# MICHA.net
KiCad netlist of a schematic drawn in EAGLE
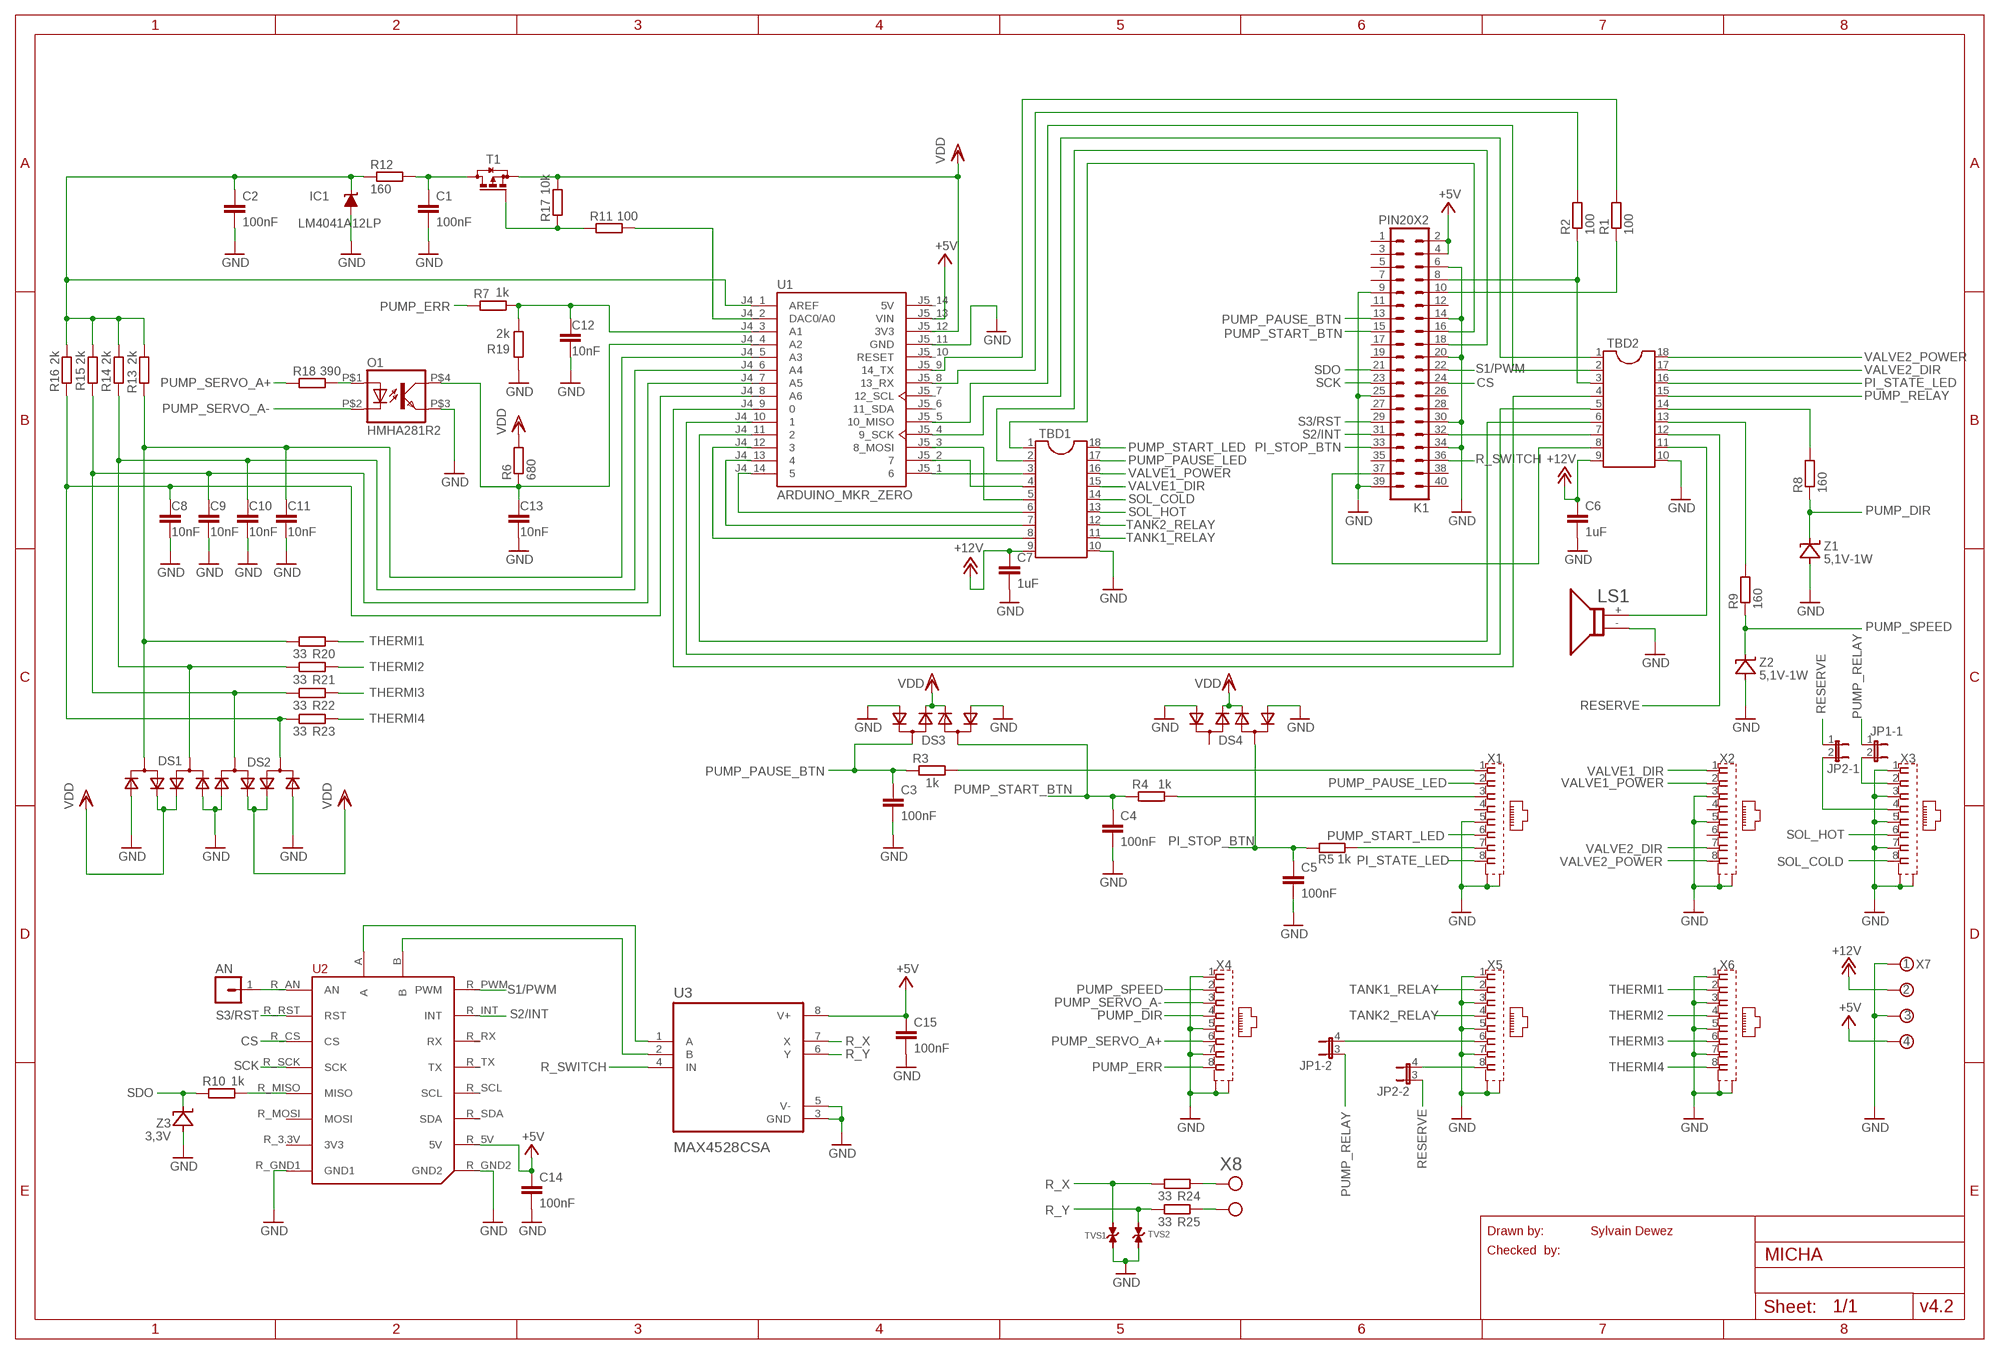
[diagram p0: schematic, sheet 1]

(export (version "E")
  (design (tool "Eeschema 10.0.6"))
  (components
    (comp (ref "AN")
      (value "MA01_PINHEADER")
      (footprint "eagle-import:MA01")
      (libsource (lib "eagle-import") (part "MA01_PINHEADER"))
    )
    (comp (ref "C1")
      (value "100nF")
      (footprint "eagle-import:C1206")
      (libsource (lib "eagle-import") (part "C-EUC1206"))
    )
    (comp (ref "C2")
      (value "100nF")
      (footprint "eagle-import:C1206")
      (libsource (lib "eagle-import") (part "C-EUC1206"))
    )
    (comp (ref "C3")
      (value "100nF")
      (footprint "eagle-import:C1206")
      (libsource (lib "eagle-import") (part "C-EUC1206"))
    )
    (comp (ref "C4")
      (value "100nF")
      (footprint "eagle-import:C1206")
      (libsource (lib "eagle-import") (part "C-EUC1206"))
    )
    (comp (ref "C5")
      (value "100nF")
      (footprint "eagle-import:C1206")
      (libsource (lib "eagle-import") (part "C-EUC1206"))
    )
    (comp (ref "C6")
      (value "1uF")
      (footprint "eagle-import:C1206")
      (libsource (lib "eagle-import") (part "C-EUC1206"))
    )
    (comp (ref "C7")
      (value "1uF")
      (footprint "eagle-import:C1206")
      (libsource (lib "eagle-import") (part "C-EUC1206"))
    )
    (comp (ref "C8")
      (value "10nF")
      (footprint "eagle-import:C1206")
      (libsource (lib "eagle-import") (part "C-EUC1206"))
    )
    (comp (ref "C9")
      (value "10nF")
      (footprint "eagle-import:C1206")
      (libsource (lib "eagle-import") (part "C-EUC1206"))
    )
    (comp (ref "C10")
      (value "10nF")
      (footprint "eagle-import:C1206")
      (libsource (lib "eagle-import") (part "C-EUC1206"))
    )
    (comp (ref "C11")
      (value "10nF")
      (footprint "eagle-import:C1206")
      (libsource (lib "eagle-import") (part "C-EUC1206"))
    )
    (comp (ref "C12")
      (value "10nF")
      (footprint "eagle-import:C1206")
      (libsource (lib "eagle-import") (part "C-EUC1206"))
    )
    (comp (ref "C13")
      (value "10nF")
      (footprint "eagle-import:C1206")
      (libsource (lib "eagle-import") (part "C-EUC1206"))
    )
    (comp (ref "C14")
      (value "100nF")
      (footprint "eagle-import:C1206")
      (libsource (lib "eagle-import") (part "C-EUC1206"))
    )
    (comp (ref "C15")
      (value "100nF")
      (footprint "eagle-import:C1206")
      (libsource (lib "eagle-import") (part "C-EUC1206"))
    )
    (comp (ref "DS1")
      (value "SDM10M45SD")
      (footprint "eagle-import:SDM10M45SD_SOT-26")
      (libsource (lib "eagle-import") (part "SDM10M45SD"))
    )
    (comp (ref "DS2")
      (value "SDM10M45SD")
      (footprint "eagle-import:SDM10M45SD_SOT-26")
      (libsource (lib "eagle-import") (part "SDM10M45SD"))
    )
    (comp (ref "DS3")
      (value "SDM10M45SD")
      (footprint "eagle-import:SDM10M45SD_SOT-26")
      (libsource (lib "eagle-import") (part "SDM10M45SD"))
    )
    (comp (ref "DS4")
      (value "SDM10M45SD")
      (footprint "eagle-import:SDM10M45SD_SOT-26")
      (libsource (lib "eagle-import") (part "SDM10M45SD"))
    )
    (comp (ref "IC1")
      (value "LM4041A12LP")
      (footprint "eagle-import:LP_O-PBCY-W3")
      (libsource (lib "eagle-import") (part "LM4041LPA12"))
    )
    (comp (ref "JP1")
      (value "JP2QE")
      (footprint "eagle-import:JP2Q")
      (libsource (lib "eagle-import") (part "JP2QE"))
    )
    (comp (ref "JP2")
      (value "JP2QE")
      (footprint "eagle-import:JP2Q")
      (libsource (lib "eagle-import") (part "JP2QE"))
    )
    (comp (ref "K1")
      (value "PIN20X2")
      (footprint "eagle-import:PIN_20X2")
      (libsource (lib "eagle-import") (part "PIN20X2"))
    )
    (comp (ref "LS1")
      (value "RSPRO-BUZZER-7800743")
      (footprint "eagle-import:RSPRO-BUZZER-7800743")
      (libsource (lib "eagle-import") (part "RSPRO-BUZZER-7800743"))
    )
    (comp (ref "O1")
      (value "HMHA281R2")
      (footprint "eagle-import:HMHA281R2")
      (libsource (lib "eagle-import") (part "HMHA281R2"))
    )
    (comp (ref "R1")
      (value "100")
      (footprint "eagle-import:R1206")
      (libsource (lib "eagle-import") (part "resistor_R-EU_R1206"))
    )
    (comp (ref "R2")
      (value "100")
      (footprint "eagle-import:R1206")
      (libsource (lib "eagle-import") (part "resistor_R-EU_R1206"))
    )
    (comp (ref "R3")
      (value "1k")
      (footprint "eagle-import:R1206")
      (libsource (lib "eagle-import") (part "resistor_R-EU_R1206"))
    )
    (comp (ref "R4")
      (value "1k")
      (footprint "eagle-import:R1206")
      (libsource (lib "eagle-import") (part "resistor_R-EU_R1206"))
    )
    (comp (ref "R5")
      (value "1k")
      (footprint "eagle-import:R1206")
      (libsource (lib "eagle-import") (part "resistor_R-EU_R1206"))
    )
    (comp (ref "R6")
      (value "680")
      (footprint "eagle-import:R1206")
      (libsource (lib "eagle-import") (part "resistor_R-EU_R1206"))
    )
    (comp (ref "R7")
      (value "1k")
      (footprint "eagle-import:R1206")
      (libsource (lib "eagle-import") (part "resistor_R-EU_R1206"))
    )
    (comp (ref "R8")
      (value "160")
      (footprint "eagle-import:R1206")
      (libsource (lib "eagle-import") (part "R-EU_R1206"))
    )
    (comp (ref "R9")
      (value "160")
      (footprint "eagle-import:R1206")
      (libsource (lib "eagle-import") (part "R-EU_R1206"))
    )
    (comp (ref "R10")
      (value "1k")
      (footprint "eagle-import:R1206")
      (libsource (lib "eagle-import") (part "resistor_R-EU_R1206"))
    )
    (comp (ref "R11")
      (value "100")
      (footprint "eagle-import:R1206")
      (libsource (lib "eagle-import") (part "resistor_R-EU_R1206"))
    )
    (comp (ref "R12")
      (value "160")
      (footprint "eagle-import:R1206")
      (libsource (lib "eagle-import") (part "R-EU_R1206"))
    )
    (comp (ref "R13")
      (value "2k")
      (footprint "eagle-import:R1206")
      (libsource (lib "eagle-import") (part "resistor_R-EU_R1206"))
    )
    (comp (ref "R14")
      (value "2k")
      (footprint "eagle-import:R1206")
      (libsource (lib "eagle-import") (part "resistor_R-EU_R1206"))
    )
    (comp (ref "R15")
      (value "2k")
      (footprint "eagle-import:R1206")
      (libsource (lib "eagle-import") (part "resistor_R-EU_R1206"))
    )
    (comp (ref "R16")
      (value "2k")
      (footprint "eagle-import:R1206")
      (libsource (lib "eagle-import") (part "resistor_R-EU_R1206"))
    )
    (comp (ref "R17")
      (value "10k")
      (footprint "eagle-import:R1206")
      (libsource (lib "eagle-import") (part "resistor_R-EU_R1206"))
    )
    (comp (ref "R18")
      (value "390")
      (footprint "eagle-import:R1206")
      (libsource (lib "eagle-import") (part "resistor_R-EU_R1206"))
    )
    (comp (ref "R19")
      (value "2k")
      (footprint "eagle-import:R1206")
      (libsource (lib "eagle-import") (part "resistor_R-EU_R1206"))
    )
    (comp (ref "R20")
      (value "33")
      (footprint "eagle-import:R1206")
      (libsource (lib "eagle-import") (part "resistor_R-EU_R1206"))
    )
    (comp (ref "R21")
      (value "33")
      (footprint "eagle-import:R1206")
      (libsource (lib "eagle-import") (part "resistor_R-EU_R1206"))
    )
    (comp (ref "R22")
      (value "33")
      (footprint "eagle-import:R1206")
      (libsource (lib "eagle-import") (part "resistor_R-EU_R1206"))
    )
    (comp (ref "R23")
      (value "33")
      (footprint "eagle-import:R1206")
      (libsource (lib "eagle-import") (part "resistor_R-EU_R1206"))
    )
    (comp (ref "R24")
      (value "33")
      (footprint "eagle-import:R1206")
      (libsource (lib "eagle-import") (part "resistor_R-EU_R1206"))
    )
    (comp (ref "R25")
      (value "33")
      (footprint "eagle-import:R1206")
      (libsource (lib "eagle-import") (part "resistor_R-EU_R1206"))
    )
    (comp (ref "T1")
      (value "BSS84")
      (footprint "eagle-import:SOT23")
      (libsource (lib "eagle-import") (part "BSS84"))
    )
    (comp (ref "TBD1")
      (value "DIL18S")
      (footprint "eagle-import:SOCKET-18")
      (libsource (lib "eagle-import") (part "DIL18S"))
    )
    (comp (ref "TBD2")
      (value "DIL18S")
      (footprint "eagle-import:SOCKET-18")
      (libsource (lib "eagle-import") (part "DIL18S"))
    )
    (comp (ref "TVS1")
      (value "TVS_SOD123")
      (footprint "eagle-import:TVS_SOD123")
      (libsource (lib "eagle-import") (part "TVS_SOD123"))
    )
    (comp (ref "TVS2")
      (value "TVS_SOD123")
      (footprint "eagle-import:TVS_SOD123")
      (libsource (lib "eagle-import") (part "TVS_SOD123"))
    )
    (comp (ref "U1")
      (value "ARDUINO_MKR_ZERO")
      (footprint "eagle-import:MODULE_ARDUINO_MKR_ZERO")
      (fields (field (name "MF") "Arduino") (field (name "MP") "ARDUINO MKR ZERO"))
      (libsource (lib "eagle-import") (part "ARDUINO_MKR_ZERO"))
    )
    (comp (ref "U2")
      (value "MIKROE_CLICK_UPGRADE")
      (footprint "eagle-import:MIKROE_BUS_MIDI_UPGRADE")
      (libsource (lib "eagle-import") (part "MIKROE_CLICK_UPGRADE"))
    )
    (comp (ref "U3")
      (value "MAX4528CSA")
      (footprint "eagle-import:SOIC127P600X175-8N")
      (fields (field (name "MF") "Maxim Integrated") (field (name "MP") "MAX4528CSA+"))
      (libsource (lib "eagle-import") (part "MAX4528CSA"))
    )
    (comp (ref "X1")
      (value "SS-7188S-A-NF_V2")
      (footprint "eagle-import:BEL_SS-7188S-A-NF")
      (fields (field (name "MF") "Stewart Connector") (field (name "MP") "SS-7188S-A-NF"))
      (libsource (lib "eagle-import") (part "SS-7188S-A-NF_V2"))
    )
    (comp (ref "X2")
      (value "SS-7188S-A-NF_V2")
      (footprint "eagle-import:BEL_SS-7188S-A-NF")
      (fields (field (name "MF") "Stewart Connector") (field (name "MP") "SS-7188S-A-NF"))
      (libsource (lib "eagle-import") (part "SS-7188S-A-NF_V2"))
    )
    (comp (ref "X3")
      (value "SS-7188S-A-NF_V2")
      (footprint "eagle-import:BEL_SS-7188S-A-NF")
      (fields (field (name "MF") "Stewart Connector") (field (name "MP") "SS-7188S-A-NF"))
      (libsource (lib "eagle-import") (part "SS-7188S-A-NF_V2"))
    )
    (comp (ref "X4")
      (value "SS-7188S-A-NF_V2")
      (footprint "eagle-import:BEL_SS-7188S-A-NF")
      (fields (field (name "MF") "Stewart Connector") (field (name "MP") "SS-7188S-A-NF"))
      (libsource (lib "eagle-import") (part "SS-7188S-A-NF_V2"))
    )
    (comp (ref "X5")
      (value "SS-7188S-A-NF_V2")
      (footprint "eagle-import:BEL_SS-7188S-A-NF")
      (fields (field (name "MF") "Stewart Connector") (field (name "MP") "SS-7188S-A-NF"))
      (libsource (lib "eagle-import") (part "SS-7188S-A-NF_V2"))
    )
    (comp (ref "X6")
      (value "SS-7188S-A-NF_V2")
      (footprint "eagle-import:BEL_SS-7188S-A-NF")
      (fields (field (name "MF") "Stewart Connector") (field (name "MP") "SS-7188S-A-NF"))
      (libsource (lib "eagle-import") (part "SS-7188S-A-NF_V2"))
    )
    (comp (ref "X7")
      (value "BUCHANAN_4_3.5MM")
      (footprint "eagle-import:BUCHANAN_4_3.5MM")
      (libsource (lib "eagle-import") (part "BUCHANAN_4_3.5MM"))
    )
    (comp (ref "X8")
      (value "MPT_0,5/_2-2,54_1725656_2")
      (footprint "eagle-import:PH_MPT_0,5__2-2,54_1725656")
      (fields (field (name "MF") "Phoenix Contact") (field (name "MP") "MPT 0,5/ 2-2,54 1725656"))
      (libsource (lib "eagle-import") (part "MPT_0,5/_2-2,54_1725656_2"))
    )
    (comp (ref "Z1")
      (value "5,1V-1W")
      (footprint "eagle-import:ZENER_SMA")
      (libsource (lib "eagle-import") (part "ZENER_SMA"))
    )
    (comp (ref "Z2")
      (value "5,1V-1W")
      (footprint "eagle-import:ZENER_SMA")
      (libsource (lib "eagle-import") (part "ZENER_SMA"))
    )
    (comp (ref "Z3")
      (value "3,3V")
      (footprint "eagle-import:ZENER_SMA")
      (libsource (lib "eagle-import") (part "ZENER_SMA"))
    )
  )
  (nets
    (net (code "1") (name "+5V") (class "Default")
      (node (ref "C14") (pin "1") (pinfunction "1_1") (pintype "passive"))
      (node (ref "C15") (pin "1") (pinfunction "1_1") (pintype "passive"))
      (node (ref "K1") (pin "2") (pinfunction "2_2") (pintype "passive"))
      (node (ref "K1") (pin "4") (pinfunction "4_4") (pintype "passive"))
      (node (ref "U1") (pin "J5_13") (pinfunction "VIN_J5_13") (pintype "power_in"))
      (node (ref "U2") (pin "R_5V") (pinfunction "5V_R_5V") (pintype "bidirectional"))
      (node (ref "U3") (pin "8") (pinfunction "V+_8") (pintype "power_in"))
      (node (ref "X7") (pin "4") (pinfunction "KL3_4") (pintype "passive"))
    )
    (net (code "2") (name "+12V") (class "Default")
      (node (ref "C6") (pin "1") (pinfunction "1_1") (pintype "passive"))
      (node (ref "C7") (pin "1") (pinfunction "1_1") (pintype "passive"))
      (node (ref "TBD1") (pin "9") (pinfunction "9_9") (pintype "passive"))
      (node (ref "TBD2") (pin "9") (pinfunction "9_9") (pintype "passive"))
      (node (ref "X7") (pin "2") (pinfunction "KL1_2") (pintype "passive"))
    )
    (net (code "3") (name "/5V") (class "Default")
      (node (ref "U1") (pin "J5_14") (pinfunction "5V_J5_14") (pintype "power_in"))
    )
    (net (code "4") (name "/CS") (class "Default")
      (node (ref "K1") (pin "24") (pinfunction "24_24") (pintype "passive"))
      (node (ref "U2") (pin "R_CS") (pinfunction "CS_R_CS") (pintype "bidirectional"))
    )
    (net (code "5") (name "/PI_STATE_LED") (class "Default")
      (node (ref "TBD2") (pin "16") (pinfunction "16_16") (pintype "passive"))
      (node (ref "X1") (pin "8") (pinfunction "8_8") (pintype "passive"))
    )
    (net (code "6") (name "/PI_STOP_BTN") (class "Default")
      (node (ref "C5") (pin "1") (pinfunction "1_1") (pintype "passive"))
      (node (ref "DS4") (pin "3") (pinfunction "C1_3") (pintype "passive"))
      (node (ref "K1") (pin "33") (pinfunction "33_33") (pintype "passive"))
      (node (ref "R5") (pin "1") (pinfunction "1_1") (pintype "passive"))
    )
    (net (code "7") (name "/PUMP_DIR") (class "Default")
      (node (ref "R8") (pin "1") (pinfunction "1_1") (pintype "passive"))
      (node (ref "X4") (pin "4") (pinfunction "4_4") (pintype "passive"))
      (node (ref "Z1") (pin "C") (pinfunction "C_C") (pintype "passive"))
    )
    (net (code "8") (name "/PUMP_ERR") (class "Default")
      (node (ref "R7") (pin "1") (pinfunction "1_1") (pintype "passive"))
      (node (ref "X4") (pin "8") (pinfunction "8_8") (pintype "passive"))
    )
    (net (code "9") (name "/PUMP_PAUSE_BTN") (class "Default")
      (node (ref "C3") (pin "1") (pinfunction "1_1") (pintype "passive"))
      (node (ref "DS3") (pin "6") (pinfunction "C_6") (pintype "passive"))
      (node (ref "K1") (pin "13") (pinfunction "13_13") (pintype "passive"))
      (node (ref "R3") (pin "1") (pinfunction "1_1") (pintype "passive"))
    )
    (net (code "10") (name "/PUMP_PAUSE_LED") (class "Default")
      (node (ref "TBD1") (pin "17") (pinfunction "17_17") (pintype "passive"))
      (node (ref "X1") (pin "2") (pinfunction "2_2") (pintype "passive"))
    )
    (net (code "11") (name "/PUMP_RELAY") (class "Default")
      (node (ref "JP1") (pin "1") (pinfunction "1_1") (pintype "passive"))
      (node (ref "JP1") (pin "3") (pinfunction "1_3") (pintype "passive"))
      (node (ref "TBD2") (pin "15") (pinfunction "15_15") (pintype "passive"))
    )
    (net (code "12") (name "/PUMP_SERVO_A+") (class "Default")
      (node (ref "R18") (pin "1") (pinfunction "1_1") (pintype "passive"))
      (node (ref "X4") (pin "6") (pinfunction "6_6") (pintype "passive"))
    )
    (net (code "13") (name "/PUMP_SERVO_A-") (class "Default")
      (node (ref "O1") (pin "P$2") (pinfunction "C_P$2") (pintype "passive"))
      (node (ref "X4") (pin "3") (pinfunction "3_3") (pintype "passive"))
    )
    (net (code "14") (name "/PUMP_SPEED") (class "Default")
      (node (ref "R9") (pin "1") (pinfunction "1_1") (pintype "passive"))
      (node (ref "X4") (pin "2") (pinfunction "2_2") (pintype "passive"))
      (node (ref "Z2") (pin "C") (pinfunction "C_C") (pintype "passive"))
    )
    (net (code "15") (name "/PUMP_START_BTN") (class "Default")
      (node (ref "C4") (pin "1") (pinfunction "1_1") (pintype "passive"))
      (node (ref "DS3") (pin "3") (pinfunction "C1_3") (pintype "passive"))
      (node (ref "K1") (pin "15") (pinfunction "15_15") (pintype "passive"))
      (node (ref "R4") (pin "1") (pinfunction "1_1") (pintype "passive"))
    )
    (net (code "16") (name "/PUMP_START_LED") (class "Default")
      (node (ref "TBD1") (pin "18") (pinfunction "18_18") (pintype "passive"))
      (node (ref "X1") (pin "6") (pinfunction "6_6") (pintype "passive"))
    )
    (net (code "17") (name "/RESERVE") (class "Default")
      (node (ref "JP2") (pin "1") (pinfunction "1_1") (pintype "passive"))
      (node (ref "JP2") (pin "3") (pinfunction "1_3") (pintype "passive"))
      (node (ref "TBD2") (pin "12") (pinfunction "12_12") (pintype "passive"))
    )
    (net (code "18") (name "/R_SWITCH") (class "Default")
      (node (ref "K1") (pin "36") (pinfunction "36_36") (pintype "passive"))
      (node (ref "U3") (pin "4") (pinfunction "IN_4") (pintype "input"))
    )
    (net (code "19") (name "/R_X") (class "Default")
      (node (ref "R24") (pin "1") (pinfunction "1_1") (pintype "passive"))
      (node (ref "TVS1") (pin "P$1") (pinfunction "C_P$1") (pintype "passive"))
      (node (ref "U3") (pin "7") (pinfunction "X_7") (pintype "output"))
    )
    (net (code "20") (name "/R_Y") (class "Default")
      (node (ref "R25") (pin "1") (pinfunction "1_1") (pintype "passive"))
      (node (ref "TVS2") (pin "P$1") (pinfunction "C_P$1") (pintype "passive"))
      (node (ref "U3") (pin "6") (pinfunction "Y_6") (pintype "output"))
    )
    (net (code "21") (name "/S1{slash}PWM") (class "Default")
      (node (ref "K1") (pin "22") (pinfunction "22_22") (pintype "passive"))
      (node (ref "U2") (pin "R_PWM") (pinfunction "PWM_R_PWM") (pintype "bidirectional"))
    )
    (net (code "22") (name "/S2{slash}INT") (class "Default")
      (node (ref "K1") (pin "31") (pinfunction "31_31") (pintype "passive"))
      (node (ref "U2") (pin "R_INT") (pinfunction "INT_R_INT") (pintype "bidirectional"))
    )
    (net (code "23") (name "/S3{slash}RST") (class "Default")
      (node (ref "K1") (pin "29") (pinfunction "29_29") (pintype "passive"))
      (node (ref "U2") (pin "R_RST") (pinfunction "RST_R_RST") (pintype "bidirectional"))
    )
    (net (code "24") (name "/SCK") (class "Default")
      (node (ref "K1") (pin "23") (pinfunction "23_23") (pintype "passive"))
      (node (ref "U2") (pin "R_SCK") (pinfunction "SCK_R_SCK") (pintype "bidirectional"))
    )
    (net (code "25") (name "/SDO") (class "Default")
      (node (ref "K1") (pin "21") (pinfunction "21_21") (pintype "passive"))
      (node (ref "R10") (pin "1") (pinfunction "1_1") (pintype "passive"))
      (node (ref "Z3") (pin "C") (pinfunction "C_C") (pintype "passive"))
    )
    (net (code "26") (name "/SOL_COLD") (class "Default")
      (node (ref "TBD1") (pin "14") (pinfunction "14_14") (pintype "passive"))
      (node (ref "X3") (pin "8") (pinfunction "8_8") (pintype "passive"))
    )
    (net (code "27") (name "/SOL_HOT") (class "Default")
      (node (ref "TBD1") (pin "13") (pinfunction "13_13") (pintype "passive"))
      (node (ref "X3") (pin "6") (pinfunction "6_6") (pintype "passive"))
    )
    (net (code "28") (name "/TANK1_RELAY") (class "Default")
      (node (ref "TBD1") (pin "11") (pinfunction "11_11") (pintype "passive"))
      (node (ref "X5") (pin "2") (pinfunction "2_2") (pintype "passive"))
    )
    (net (code "29") (name "/TANK2_RELAY") (class "Default")
      (node (ref "TBD1") (pin "12") (pinfunction "12_12") (pintype "passive"))
      (node (ref "X5") (pin "4") (pinfunction "4_4") (pintype "passive"))
    )
    (net (code "30") (name "/THERMI1") (class "Default")
      (node (ref "R20") (pin "2") (pinfunction "2_2") (pintype "passive"))
      (node (ref "X6") (pin "2") (pinfunction "2_2") (pintype "passive"))
    )
    (net (code "31") (name "/THERMI2") (class "Default")
      (node (ref "R21") (pin "2") (pinfunction "2_2") (pintype "passive"))
      (node (ref "X6") (pin "4") (pinfunction "4_4") (pintype "passive"))
    )
    (net (code "32") (name "/THERMI3") (class "Default")
      (node (ref "R22") (pin "2") (pinfunction "2_2") (pintype "passive"))
      (node (ref "X6") (pin "6") (pinfunction "6_6") (pintype "passive"))
    )
    (net (code "33") (name "/THERMI4") (class "Default")
      (node (ref "R23") (pin "2") (pinfunction "2_2") (pintype "passive"))
      (node (ref "X6") (pin "8") (pinfunction "8_8") (pintype "passive"))
    )
    (net (code "34") (name "/VALVE1_DIR") (class "Default")
      (node (ref "TBD1") (pin "15") (pinfunction "15_15") (pintype "passive"))
      (node (ref "X2") (pin "1") (pinfunction "1_1") (pintype "passive"))
    )
    (net (code "35") (name "/VALVE1_POWER") (class "Default")
      (node (ref "TBD1") (pin "16") (pinfunction "16_16") (pintype "passive"))
      (node (ref "X2") (pin "2") (pinfunction "2_2") (pintype "passive"))
    )
    (net (code "36") (name "/VALVE2_DIR") (class "Default")
      (node (ref "TBD2") (pin "17") (pinfunction "17_17") (pintype "passive"))
      (node (ref "X2") (pin "7") (pinfunction "7_7") (pintype "passive"))
    )
    (net (code "37") (name "/VALVE2_POWER") (class "Default")
      (node (ref "TBD2") (pin "18") (pinfunction "18_18") (pintype "passive"))
      (node (ref "X2") (pin "8") (pinfunction "8_8") (pintype "passive"))
    )
    (net (code "38") (name "GND") (class "Default")
      (node (ref "C1") (pin "2") (pinfunction "2_2") (pintype "passive"))
      (node (ref "C10") (pin "2") (pinfunction "2_2") (pintype "passive"))
      (node (ref "C11") (pin "2") (pinfunction "2_2") (pintype "passive"))
      (node (ref "C12") (pin "2") (pinfunction "2_2") (pintype "passive"))
      (node (ref "C13") (pin "2") (pinfunction "2_2") (pintype "passive"))
      (node (ref "C14") (pin "2") (pinfunction "2_2") (pintype "passive"))
      (node (ref "C15") (pin "2") (pinfunction "2_2") (pintype "passive"))
      (node (ref "C2") (pin "2") (pinfunction "2_2") (pintype "passive"))
      (node (ref "C3") (pin "2") (pinfunction "2_2") (pintype "passive"))
      (node (ref "C4") (pin "2") (pinfunction "2_2") (pintype "passive"))
      (node (ref "C5") (pin "2") (pinfunction "2_2") (pintype "passive"))
      (node (ref "C6") (pin "2") (pinfunction "2_2") (pintype "passive"))
      (node (ref "C7") (pin "2") (pinfunction "2_2") (pintype "passive"))
      (node (ref "C8") (pin "2") (pinfunction "2_2") (pintype "passive"))
      (node (ref "C9") (pin "2") (pinfunction "2_2") (pintype "passive"))
      (node (ref "DS1") (pin "1") (pinfunction "A2_1") (pintype "passive"))
      (node (ref "DS1") (pin "4") (pinfunction "A3_4") (pintype "passive"))
      (node (ref "DS2") (pin "1") (pinfunction "A2_1") (pintype "passive"))
      (node (ref "DS2") (pin "4") (pinfunction "A3_4") (pintype "passive"))
      (node (ref "DS3") (pin "1") (pinfunction "A2_1") (pintype "passive"))
      (node (ref "DS3") (pin "4") (pinfunction "A3_4") (pintype "passive"))
      (node (ref "DS4") (pin "1") (pinfunction "A2_1") (pintype "passive"))
      (node (ref "DS4") (pin "4") (pinfunction "A3_4") (pintype "passive"))
      (node (ref "IC1") (pin "3") (pinfunction "A_3") (pintype "passive"))
      (node (ref "K1") (pin "14") (pinfunction "14_14") (pintype "passive"))
      (node (ref "K1") (pin "20") (pinfunction "20_20") (pintype "passive"))
      (node (ref "K1") (pin "25") (pinfunction "25_25") (pintype "passive"))
      (node (ref "K1") (pin "30") (pinfunction "30_30") (pintype "passive"))
      (node (ref "K1") (pin "34") (pinfunction "34_34") (pintype "passive"))
      (node (ref "K1") (pin "39") (pinfunction "39_39") (pintype "passive"))
      (node (ref "K1") (pin "6") (pinfunction "6_6") (pintype "passive"))
      (node (ref "K1") (pin "9") (pinfunction "9_9") (pintype "passive"))
      (node (ref "LS1") (pin "-") (pinfunction "2_-") (pintype "passive"))
      (node (ref "O1") (pin "P$3") (pinfunction "EMIT_P$3") (pintype "passive"))
      (node (ref "R19") (pin "1") (pinfunction "1_1") (pintype "passive"))
      (node (ref "TBD1") (pin "10") (pinfunction "10_10") (pintype "passive"))
      (node (ref "TBD2") (pin "10") (pinfunction "10_10") (pintype "passive"))
      (node (ref "TVS1") (pin "P$2") (pinfunction "C1_P$2") (pintype "passive"))
      (node (ref "TVS2") (pin "P$2") (pinfunction "C1_P$2") (pintype "passive"))
      (node (ref "U1") (pin "J5_11") (pinfunction "GND_J5_11") (pintype "power_in"))
      (node (ref "U2") (pin "R_GND1") (pinfunction "GND1_R_GND1") (pintype "bidirectional"))
      (node (ref "U2") (pin "R_GND2") (pinfunction "GND2_R_GND2") (pintype "bidirectional"))
      (node (ref "U3") (pin "3") (pinfunction "GND_3") (pintype "power_in"))
      (node (ref "U3") (pin "5") (pinfunction "V-_5") (pintype "power_in"))
      (node (ref "X1") (pin "5") (pinfunction "5_5") (pintype "passive"))
      (node (ref "X1") (pin "S1") (pinfunction "GND1_S1") (pintype "passive"))
      (node (ref "X1") (pin "S2") (pinfunction "GND2_S2") (pintype "passive"))
      (node (ref "X2") (pin "3") (pinfunction "3_3") (pintype "passive"))
      (node (ref "X2") (pin "5") (pinfunction "5_5") (pintype "passive"))
      (node (ref "X2") (pin "S1") (pinfunction "GND1_S1") (pintype "passive"))
      (node (ref "X2") (pin "S2") (pinfunction "GND2_S2") (pintype "passive"))
      (node (ref "X3") (pin "1") (pinfunction "1_1") (pintype "passive"))
      (node (ref "X3") (pin "3") (pinfunction "3_3") (pintype "passive"))
      (node (ref "X3") (pin "5") (pinfunction "5_5") (pintype "passive"))
      (node (ref "X3") (pin "7") (pinfunction "7_7") (pintype "passive"))
      (node (ref "X3") (pin "S1") (pinfunction "GND1_S1") (pintype "passive"))
      (node (ref "X3") (pin "S2") (pinfunction "GND2_S2") (pintype "passive"))
      (node (ref "X4") (pin "1") (pinfunction "1_1") (pintype "passive"))
      (node (ref "X4") (pin "5") (pinfunction "5_5") (pintype "passive"))
      (node (ref "X4") (pin "7") (pinfunction "7_7") (pintype "passive"))
      (node (ref "X4") (pin "S1") (pinfunction "GND1_S1") (pintype "passive"))
      (node (ref "X4") (pin "S2") (pinfunction "GND2_S2") (pintype "passive"))
      (node (ref "X5") (pin "1") (pinfunction "1_1") (pintype "passive"))
      (node (ref "X5") (pin "3") (pinfunction "3_3") (pintype "passive"))
      (node (ref "X5") (pin "5") (pinfunction "5_5") (pintype "passive"))
      (node (ref "X5") (pin "7") (pinfunction "7_7") (pintype "passive"))
      (node (ref "X5") (pin "S1") (pinfunction "GND1_S1") (pintype "passive"))
      (node (ref "X5") (pin "S2") (pinfunction "GND2_S2") (pintype "passive"))
      (node (ref "X6") (pin "1") (pinfunction "1_1") (pintype "passive"))
      (node (ref "X6") (pin "3") (pinfunction "3_3") (pintype "passive"))
      (node (ref "X6") (pin "5") (pinfunction "5_5") (pintype "passive"))
      (node (ref "X6") (pin "7") (pinfunction "7_7") (pintype "passive"))
      (node (ref "X6") (pin "S1") (pinfunction "GND1_S1") (pintype "passive"))
      (node (ref "X6") (pin "S2") (pinfunction "GND2_S2") (pintype "passive"))
      (node (ref "X7") (pin "1") (pinfunction "KL_1") (pintype "passive"))
      (node (ref "X7") (pin "3") (pinfunction "KL2_3") (pintype "passive"))
      (node (ref "Z1") (pin "A") (pinfunction "A_A") (pintype "passive"))
      (node (ref "Z2") (pin "A") (pinfunction "A_A") (pintype "passive"))
      (node (ref "Z3") (pin "A") (pinfunction "A_A") (pintype "passive"))
    )
    (net (code "39") (name "Net-(DS1-C)") (class "Default")
      (node (ref "C10") (pin "1") (pinfunction "1_1") (pintype "passive"))
      (node (ref "DS1") (pin "6") (pinfunction "C_6") (pintype "passive"))
      (node (ref "R14") (pin "2") (pinfunction "2_2") (pintype "passive"))
      (node (ref "R21") (pin "1") (pinfunction "1_1") (pintype "passive"))
      (node (ref "U1") (pin "J4_6") (pinfunction "A4_J4_6") (pintype "bidirectional"))
    )
    (net (code "40") (name "Net-(DS1-C1)") (class "Default")
      (node (ref "C11") (pin "1") (pinfunction "1_1") (pintype "passive"))
      (node (ref "DS1") (pin "3") (pinfunction "C1_3") (pintype "passive"))
      (node (ref "R13") (pin "2") (pinfunction "2_2") (pintype "passive"))
      (node (ref "R20") (pin "1") (pinfunction "1_1") (pintype "passive"))
      (node (ref "U1") (pin "J4_5") (pinfunction "A3_J4_5") (pintype "bidirectional"))
    )
    (net (code "41") (name "Net-(DS2-C)") (class "Default")
      (node (ref "C8") (pin "1") (pinfunction "1_1") (pintype "passive"))
      (node (ref "DS2") (pin "6") (pinfunction "C_6") (pintype "passive"))
      (node (ref "R16") (pin "2") (pinfunction "2_2") (pintype "passive"))
      (node (ref "R23") (pin "1") (pinfunction "1_1") (pintype "passive"))
      (node (ref "U1") (pin "J4_8") (pinfunction "A6_J4_8") (pintype "bidirectional"))
    )
    (net (code "42") (name "Net-(DS2-C1)") (class "Default")
      (node (ref "C9") (pin "1") (pinfunction "1_1") (pintype "passive"))
      (node (ref "DS2") (pin "3") (pinfunction "C1_3") (pintype "passive"))
      (node (ref "R15") (pin "2") (pinfunction "2_2") (pintype "passive"))
      (node (ref "R22") (pin "1") (pinfunction "1_1") (pintype "passive"))
      (node (ref "U1") (pin "J4_7") (pinfunction "A5_J4_7") (pintype "bidirectional"))
    )
    (net (code "43") (name "Net-(IC1-C)") (class "Default")
      (node (ref "C2") (pin "1") (pinfunction "1_1") (pintype "passive"))
      (node (ref "IC1") (pin "2") (pinfunction "C_2") (pintype "passive"))
      (node (ref "R12") (pin "1") (pinfunction "1_1") (pintype "passive"))
      (node (ref "R13") (pin "1") (pinfunction "1_1") (pintype "passive"))
      (node (ref "R14") (pin "1") (pinfunction "1_1") (pintype "passive"))
      (node (ref "R15") (pin "1") (pinfunction "1_1") (pintype "passive"))
      (node (ref "R16") (pin "1") (pinfunction "1_1") (pintype "passive"))
      (node (ref "U1") (pin "J4_1") (pinfunction "AREF_J4_1") (pintype "bidirectional"))
    )
    (net (code "44") (name "Net-(JP1-Pad2)") (class "Default")
      (node (ref "JP1") (pin "2") (pinfunction "2_2") (pintype "passive"))
      (node (ref "X3") (pin "2") (pinfunction "2_2") (pintype "passive"))
    )
    (net (code "45") (name "Net-(JP1B-2)") (class "Default")
      (node (ref "JP1") (pin "4") (pinfunction "2_4") (pintype "passive"))
      (node (ref "X5") (pin "6") (pinfunction "6_6") (pintype "passive"))
    )
    (net (code "46") (name "Net-(JP2-Pad2)") (class "Default")
      (node (ref "JP2") (pin "2") (pinfunction "2_2") (pintype "passive"))
      (node (ref "X3") (pin "4") (pinfunction "4_4") (pintype "passive"))
    )
    (net (code "47") (name "Net-(JP2B-2)") (class "Default")
      (node (ref "JP2") (pin "4") (pinfunction "2_4") (pintype "passive"))
      (node (ref "X5") (pin "8") (pinfunction "8_8") (pintype "passive"))
    )
    (net (code "48") (name "Net-(K1-Pad8)") (class "Default")
      (node (ref "K1") (pin "8") (pinfunction "8_8") (pintype "passive"))
      (node (ref "R2") (pin "1") (pinfunction "1_1") (pintype "passive"))
      (node (ref "TBD2") (pin "3") (pinfunction "3_3") (pintype "passive"))
    )
    (net (code "49") (name "Net-(K1-Pad10)") (class "Default")
      (node (ref "K1") (pin "10") (pinfunction "10_10") (pintype "passive"))
      (node (ref "R1") (pin "1") (pinfunction "1_1") (pintype "passive"))
    )
    (net (code "50") (name "Net-(K1-Pad16)") (class "Default")
      (node (ref "K1") (pin "16") (pinfunction "16_16") (pintype "passive"))
      (node (ref "TBD1") (pin "1") (pinfunction "1_1") (pintype "passive"))
    )
    (net (code "51") (name "Net-(K1-Pad18)") (class "Default")
      (node (ref "K1") (pin "18") (pinfunction "18_18") (pintype "passive"))
      (node (ref "TBD1") (pin "2") (pinfunction "2_2") (pintype "passive"))
    )
    (net (code "52") (name "Net-(K1-Pad32)") (class "Default")
      (node (ref "K1") (pin "32") (pinfunction "32_32") (pintype "passive"))
      (node (ref "TBD2") (pin "7") (pinfunction "7_7") (pintype "passive"))
    )
    (net (code "53") (name "Net-(K1-Pad37)") (class "Default")
      (node (ref "K1") (pin "37") (pinfunction "37_37") (pintype "passive"))
      (node (ref "TBD2") (pin "8") (pinfunction "8_8") (pintype "passive"))
    )
    (net (code "54") (name "Net-(LS1-1)") (class "Default")
      (node (ref "LS1") (pin "+") (pinfunction "1_+") (pintype "passive"))
      (node (ref "TBD2") (pin "11") (pinfunction "11_11") (pintype "passive"))
    )
    (net (code "55") (name "Net-(O1-A)") (class "Default")
      (node (ref "O1") (pin "P$1") (pinfunction "A_P$1") (pintype "passive"))
      (node (ref "R18") (pin "2") (pinfunction "2_2") (pintype "passive"))
    )
    (net (code "56") (name "Net-(O1-COL)") (class "Default")
      (node (ref "C13") (pin "1") (pinfunction "1_1") (pintype "passive"))
      (node (ref "O1") (pin "P$4") (pinfunction "COL_P$4") (pintype "passive"))
      (node (ref "R6") (pin "1") (pinfunction "1_1") (pintype "passive"))
      (node (ref "U1") (pin "J4_4") (pinfunction "A2_J4_4") (pintype "bidirectional"))
    )
    (net (code "57") (name "Net-(R3-Pad2)") (class "Default")
      (node (ref "R3") (pin "2") (pinfunction "2_2") (pintype "passive"))
      (node (ref "X1") (pin "1") (pinfunction "1_1") (pintype "passive"))
    )
    (net (code "58") (name "Net-(R4-Pad2)") (class "Default")
      (node (ref "R4") (pin "2") (pinfunction "2_2") (pintype "passive"))
      (node (ref "X1") (pin "3") (pinfunction "3_3") (pintype "passive"))
    )
    (net (code "59") (name "Net-(R5-Pad2)") (class "Default")
      (node (ref "R5") (pin "2") (pinfunction "2_2") (pintype "passive"))
      (node (ref "X1") (pin "7") (pinfunction "7_7") (pintype "passive"))
    )
    (net (code "60") (name "Net-(R8-Pad2)") (class "Default")
      (node (ref "R8") (pin "2") (pinfunction "2_2") (pintype "passive"))
      (node (ref "TBD2") (pin "14") (pinfunction "14_14") (pintype "passive"))
    )
    (net (code "61") (name "Net-(R9-Pad2)") (class "Default")
      (node (ref "R9") (pin "2") (pinfunction "2_2") (pintype "passive"))
      (node (ref "TBD2") (pin "13") (pinfunction "13_13") (pintype "passive"))
    )
    (net (code "62") (name "Net-(T1-D)") (class "Default")
      (node (ref "C1") (pin "1") (pinfunction "1_1") (pintype "passive"))
      (node (ref "R12") (pin "2") (pinfunction "2_2") (pintype "passive"))
      (node (ref "T1") (pin "3") (pinfunction "D_3") (pintype "passive"))
    )
    (net (code "63") (name "Net-(T1-G)") (class "Default")
      (node (ref "R11") (pin "1") (pinfunction "1_1") (pintype "passive"))
      (node (ref "R17") (pin "1") (pinfunction "1_1") (pintype "passive"))
      (node (ref "T1") (pin "1") (pinfunction "G_1") (pintype "passive"))
    )
    (net (code "64") (name "Net-(U1-0)") (class "Default")
      (node (ref "TBD2") (pin "4") (pinfunction "4_4") (pintype "passive"))
      (node (ref "U1") (pin "J4_9") (pinfunction "0_J4_9") (pintype "bidirectional"))
    )
    (net (code "65") (name "Net-(U1-1)") (class "Default")
      (node (ref "TBD2") (pin "5") (pinfunction "5_5") (pintype "passive"))
      (node (ref "U1") (pin "J4_10") (pinfunction "1_J4_10") (pintype "bidirectional"))
    )
    (net (code "66") (name "Net-(U1-2)") (class "Default")
      (node (ref "TBD2") (pin "6") (pinfunction "6_6") (pintype "passive"))
      (node (ref "U1") (pin "J4_11") (pinfunction "2_J4_11") (pintype "bidirectional"))
    )
    (net (code "67") (name "Net-(U1-3)") (class "Default")
      (node (ref "TBD1") (pin "8") (pinfunction "8_8") (pintype "passive"))
      (node (ref "U1") (pin "J4_12") (pinfunction "3_J4_12") (pintype "bidirectional"))
    )
    (net (code "68") (name "Net-(U1-4)") (class "Default")
      (node (ref "TBD1") (pin "7") (pinfunction "7_7") (pintype "passive"))
      (node (ref "U1") (pin "J4_13") (pinfunction "4_J4_13") (pintype "bidirectional"))
    )
    (net (code "69") (name "Net-(U1-5)") (class "Default")
      (node (ref "TBD1") (pin "6") (pinfunction "6_6") (pintype "passive"))
      (node (ref "U1") (pin "J4_14") (pinfunction "5_J4_14") (pintype "bidirectional"))
    )
    (net (code "70") (name "Net-(U1-6)") (class "Default")
      (node (ref "TBD1") (pin "3") (pinfunction "3_3") (pintype "passive"))
      (node (ref "U1") (pin "J5_1") (pinfunction "6_J5_1") (pintype "bidirectional"))
    )
    (net (code "71") (name "Net-(U1-7)") (class "Default")
      (node (ref "TBD1") (pin "4") (pinfunction "4_4") (pintype "passive"))
      (node (ref "U1") (pin "J5_2") (pinfunction "7_J5_2") (pintype "bidirectional"))
    )
    (net (code "72") (name "Net-(U1-8_MOSI)") (class "Default")
      (node (ref "TBD1") (pin "5") (pinfunction "5_5") (pintype "passive"))
      (node (ref "U1") (pin "J5_3") (pinfunction "8_MOSI_J5_3") (pintype "bidirectional"))
    )
    (net (code "73") (name "Net-(U1-9_SCK)") (class "Default")
      (node (ref "TBD2") (pin "1") (pinfunction "1_1") (pintype "passive"))
      (node (ref "U1") (pin "J5_4") (pinfunction "9_SCK_J5_4") (pintype "bidirectional"))
    )
    (net (code "74") (name "Net-(U1-10_MISO)") (class "Default")
      (node (ref "TBD2") (pin "2") (pinfunction "2_2") (pintype "passive"))
      (node (ref "U1") (pin "J5_5") (pinfunction "10_MISO_J5_5") (pintype "bidirectional"))
    )
    (net (code "75") (name "Net-(U1-13_RX)") (class "Default")
      (node (ref "R2") (pin "2") (pinfunction "2_2") (pintype "passive"))
      (node (ref "U1") (pin "J5_8") (pinfunction "13_RX_J5_8") (pintype "input"))
    )
    (net (code "76") (name "Net-(U1-14_TX)") (class "Default")
      (node (ref "R1") (pin "2") (pinfunction "2_2") (pintype "passive"))
      (node (ref "U1") (pin "J5_9") (pinfunction "14_TX_J5_9") (pintype "output"))
    )
    (net (code "77") (name "Net-(U1-A1)") (class "Default")
      (node (ref "C12") (pin "1") (pinfunction "1_1") (pintype "passive"))
      (node (ref "R19") (pin "2") (pinfunction "2_2") (pintype "passive"))
      (node (ref "R7") (pin "2") (pinfunction "2_2") (pintype "passive"))
      (node (ref "U1") (pin "J4_3") (pinfunction "A1_J4_3") (pintype "bidirectional"))
    )
    (net (code "78") (name "Net-(U1-DAC0{slash}A0)") (class "Default")
      (node (ref "R11") (pin "2") (pinfunction "2_2") (pintype "passive"))
      (node (ref "U1") (pin "J4_2") (pinfunction "DAC0/A0_J4_2") (pintype "bidirectional"))
    )
    (net (code "79") (name "Net-(U2-AN)") (class "Default")
      (node (ref "AN") (pin "1") (pinfunction "1_1") (pintype "passive"))
      (node (ref "U2") (pin "R_AN") (pinfunction "AN_R_AN") (pintype "bidirectional"))
    )
    (net (code "80") (name "Net-(U2-MISO)") (class "Default")
      (node (ref "R10") (pin "2") (pinfunction "2_2") (pintype "passive"))
      (node (ref "U2") (pin "R_MISO") (pinfunction "MISO_R_MISO") (pintype "bidirectional"))
    )
    (net (code "81") (name "Net-(U3-A)") (class "Default")
      (node (ref "U2") (pin "A") (pinfunction "A_A") (pintype "bidirectional"))
      (node (ref "U3") (pin "1") (pinfunction "A_1") (pintype "input"))
    )
    (net (code "82") (name "Net-(U3-B)") (class "Default")
      (node (ref "U2") (pin "B") (pinfunction "B_B") (pintype "bidirectional"))
      (node (ref "U3") (pin "2") (pinfunction "B_2") (pintype "input"))
    )
    (net (code "83") (name "Net-(X8-KL)") (class "Default")
      (node (ref "R25") (pin "2") (pinfunction "2_2") (pintype "passive"))
      (node (ref "X8") (pin "1") (pinfunction "KL_1") (pintype "passive"))
    )
    (net (code "84") (name "Net-(X8-KL1)") (class "Default")
      (node (ref "R24") (pin "2") (pinfunction "2_2") (pintype "passive"))
      (node (ref "X8") (pin "2") (pinfunction "KL1_2") (pintype "passive"))
    )
    (net (code "85") (name "VDD") (class "Default")
      (node (ref "DS1") (pin "2") (pinfunction "A1_2") (pintype "passive"))
      (node (ref "DS1") (pin "5") (pinfunction "A4_5") (pintype "passive"))
      (node (ref "DS2") (pin "2") (pinfunction "A1_2") (pintype "passive"))
      (node (ref "DS2") (pin "5") (pinfunction "A4_5") (pintype "passive"))
      (node (ref "DS3") (pin "2") (pinfunction "A1_2") (pintype "passive"))
      (node (ref "DS3") (pin "5") (pinfunction "A4_5") (pintype "passive"))
      (node (ref "DS4") (pin "2") (pinfunction "A1_2") (pintype "passive"))
      (node (ref "DS4") (pin "5") (pinfunction "A4_5") (pintype "passive"))
      (node (ref "R17") (pin "2") (pinfunction "2_2") (pintype "passive"))
      (node (ref "R6") (pin "2") (pinfunction "2_2") (pintype "passive"))
      (node (ref "T1") (pin "2") (pinfunction "S_2") (pintype "passive"))
      (node (ref "U1") (pin "J5_12") (pinfunction "3V3_J5_12") (pintype "power_in"))
    )
    (net (code "86") (name "unconnected-(DS4-C-Pad6)") (class "Default")
      (node (ref "DS4") (pin "6") (pinfunction "C_6") (pintype "passive"))
    )
    (net (code "87") (name "unconnected-(K1-Pad1)") (class "Default")
      (node (ref "K1") (pin "1") (pinfunction "1_1") (pintype "passive"))
    )
    (net (code "88") (name "unconnected-(K1-Pad3)") (class "Default")
      (node (ref "K1") (pin "3") (pinfunction "3_3") (pintype "passive"))
    )
    (net (code "89") (name "unconnected-(K1-Pad5)") (class "Default")
      (node (ref "K1") (pin "5") (pinfunction "5_5") (pintype "passive"))
    )
    (net (code "90") (name "unconnected-(K1-Pad7)") (class "Default")
      (node (ref "K1") (pin "7") (pinfunction "7_7") (pintype "passive"))
    )
    (net (code "91") (name "unconnected-(K1-Pad11)") (class "Default")
      (node (ref "K1") (pin "11") (pinfunction "11_11") (pintype "passive"))
    )
    (net (code "92") (name "unconnected-(K1-Pad12)") (class "Default")
      (node (ref "K1") (pin "12") (pinfunction "12_12") (pintype "passive"))
    )
    (net (code "93") (name "unconnected-(K1-Pad17)") (class "Default")
      (node (ref "K1") (pin "17") (pinfunction "17_17") (pintype "passive"))
    )
    (net (code "94") (name "unconnected-(K1-Pad19)") (class "Default")
      (node (ref "K1") (pin "19") (pinfunction "19_19") (pintype "passive"))
    )
    (net (code "95") (name "unconnected-(K1-Pad26)") (class "Default")
      (node (ref "K1") (pin "26") (pinfunction "26_26") (pintype "passive"))
    )
    (net (code "96") (name "unconnected-(K1-Pad27)") (class "Default")
      (node (ref "K1") (pin "27") (pinfunction "27_27") (pintype "passive"))
    )
    (net (code "97") (name "unconnected-(K1-Pad28)") (class "Default")
      (node (ref "K1") (pin "28") (pinfunction "28_28") (pintype "passive"))
    )
    (net (code "98") (name "unconnected-(K1-Pad35)") (class "Default")
      (node (ref "K1") (pin "35") (pinfunction "35_35") (pintype "passive"))
    )
    (net (code "99") (name "unconnected-(K1-Pad38)") (class "Default")
      (node (ref "K1") (pin "38") (pinfunction "38_38") (pintype "passive"))
    )
    (net (code "100") (name "unconnected-(K1-Pad40)") (class "Default")
      (node (ref "K1") (pin "40") (pinfunction "40_40") (pintype "passive"))
    )
    (net (code "101") (name "unconnected-(U1-11_SDA-PadJ5_6)") (class "Default")
      (node (ref "U1") (pin "J5_6") (pinfunction "11_SDA_J5_6") (pintype "bidirectional"))
    )
    (net (code "102") (name "unconnected-(U1-12_SCL-PadJ5_7)") (class "Default")
      (node (ref "U1") (pin "J5_7") (pinfunction "12_SCL_J5_7") (pintype "bidirectional"))
    )
    (net (code "103") (name "unconnected-(U1-RESET-PadJ5_10)") (class "Default")
      (node (ref "U1") (pin "J5_10") (pinfunction "RESET_J5_10") (pintype "bidirectional"))
    )
    (net (code "104") (name "unconnected-(U2-3V3-PadR_3.3V)") (class "Default")
      (node (ref "U2") (pin "R_3.3V") (pinfunction "3V3_R_3.3V") (pintype "bidirectional"))
    )
    (net (code "105") (name "unconnected-(U2-MOSI-PadR_MOSI)") (class "Default")
      (node (ref "U2") (pin "R_MOSI") (pinfunction "MOSI_R_MOSI") (pintype "bidirectional"))
    )
    (net (code "106") (name "unconnected-(U2-RX-PadR_RX)") (class "Default")
      (node (ref "U2") (pin "R_RX") (pinfunction "RX_R_RX") (pintype "bidirectional"))
    )
    (net (code "107") (name "unconnected-(U2-SCL-PadR_SCL)") (class "Default")
      (node (ref "U2") (pin "R_SCL") (pinfunction "SCL_R_SCL") (pintype "bidirectional"))
    )
    (net (code "108") (name "unconnected-(U2-SDA-PadR_SDA)") (class "Default")
      (node (ref "U2") (pin "R_SDA") (pinfunction "SDA_R_SDA") (pintype "bidirectional"))
    )
    (net (code "109") (name "unconnected-(U2-TX-PadR_TX)") (class "Default")
      (node (ref "U2") (pin "R_TX") (pinfunction "TX_R_TX") (pintype "bidirectional"))
    )
    (net (code "110") (name "unconnected-(X1-Pad4)") (class "Default")
      (node (ref "X1") (pin "4") (pinfunction "4_4") (pintype "passive"))
    )
    (net (code "111") (name "unconnected-(X2-Pad4)") (class "Default")
      (node (ref "X2") (pin "4") (pinfunction "4_4") (pintype "passive"))
    )
    (net (code "112") (name "unconnected-(X2-Pad6)") (class "Default")
      (node (ref "X2") (pin "6") (pinfunction "6_6") (pintype "passive"))
    )
  )
)
